# 1_ESP32_schematic_schdoc.net
KiCad netlist of a schematic drawn in Altium Designer
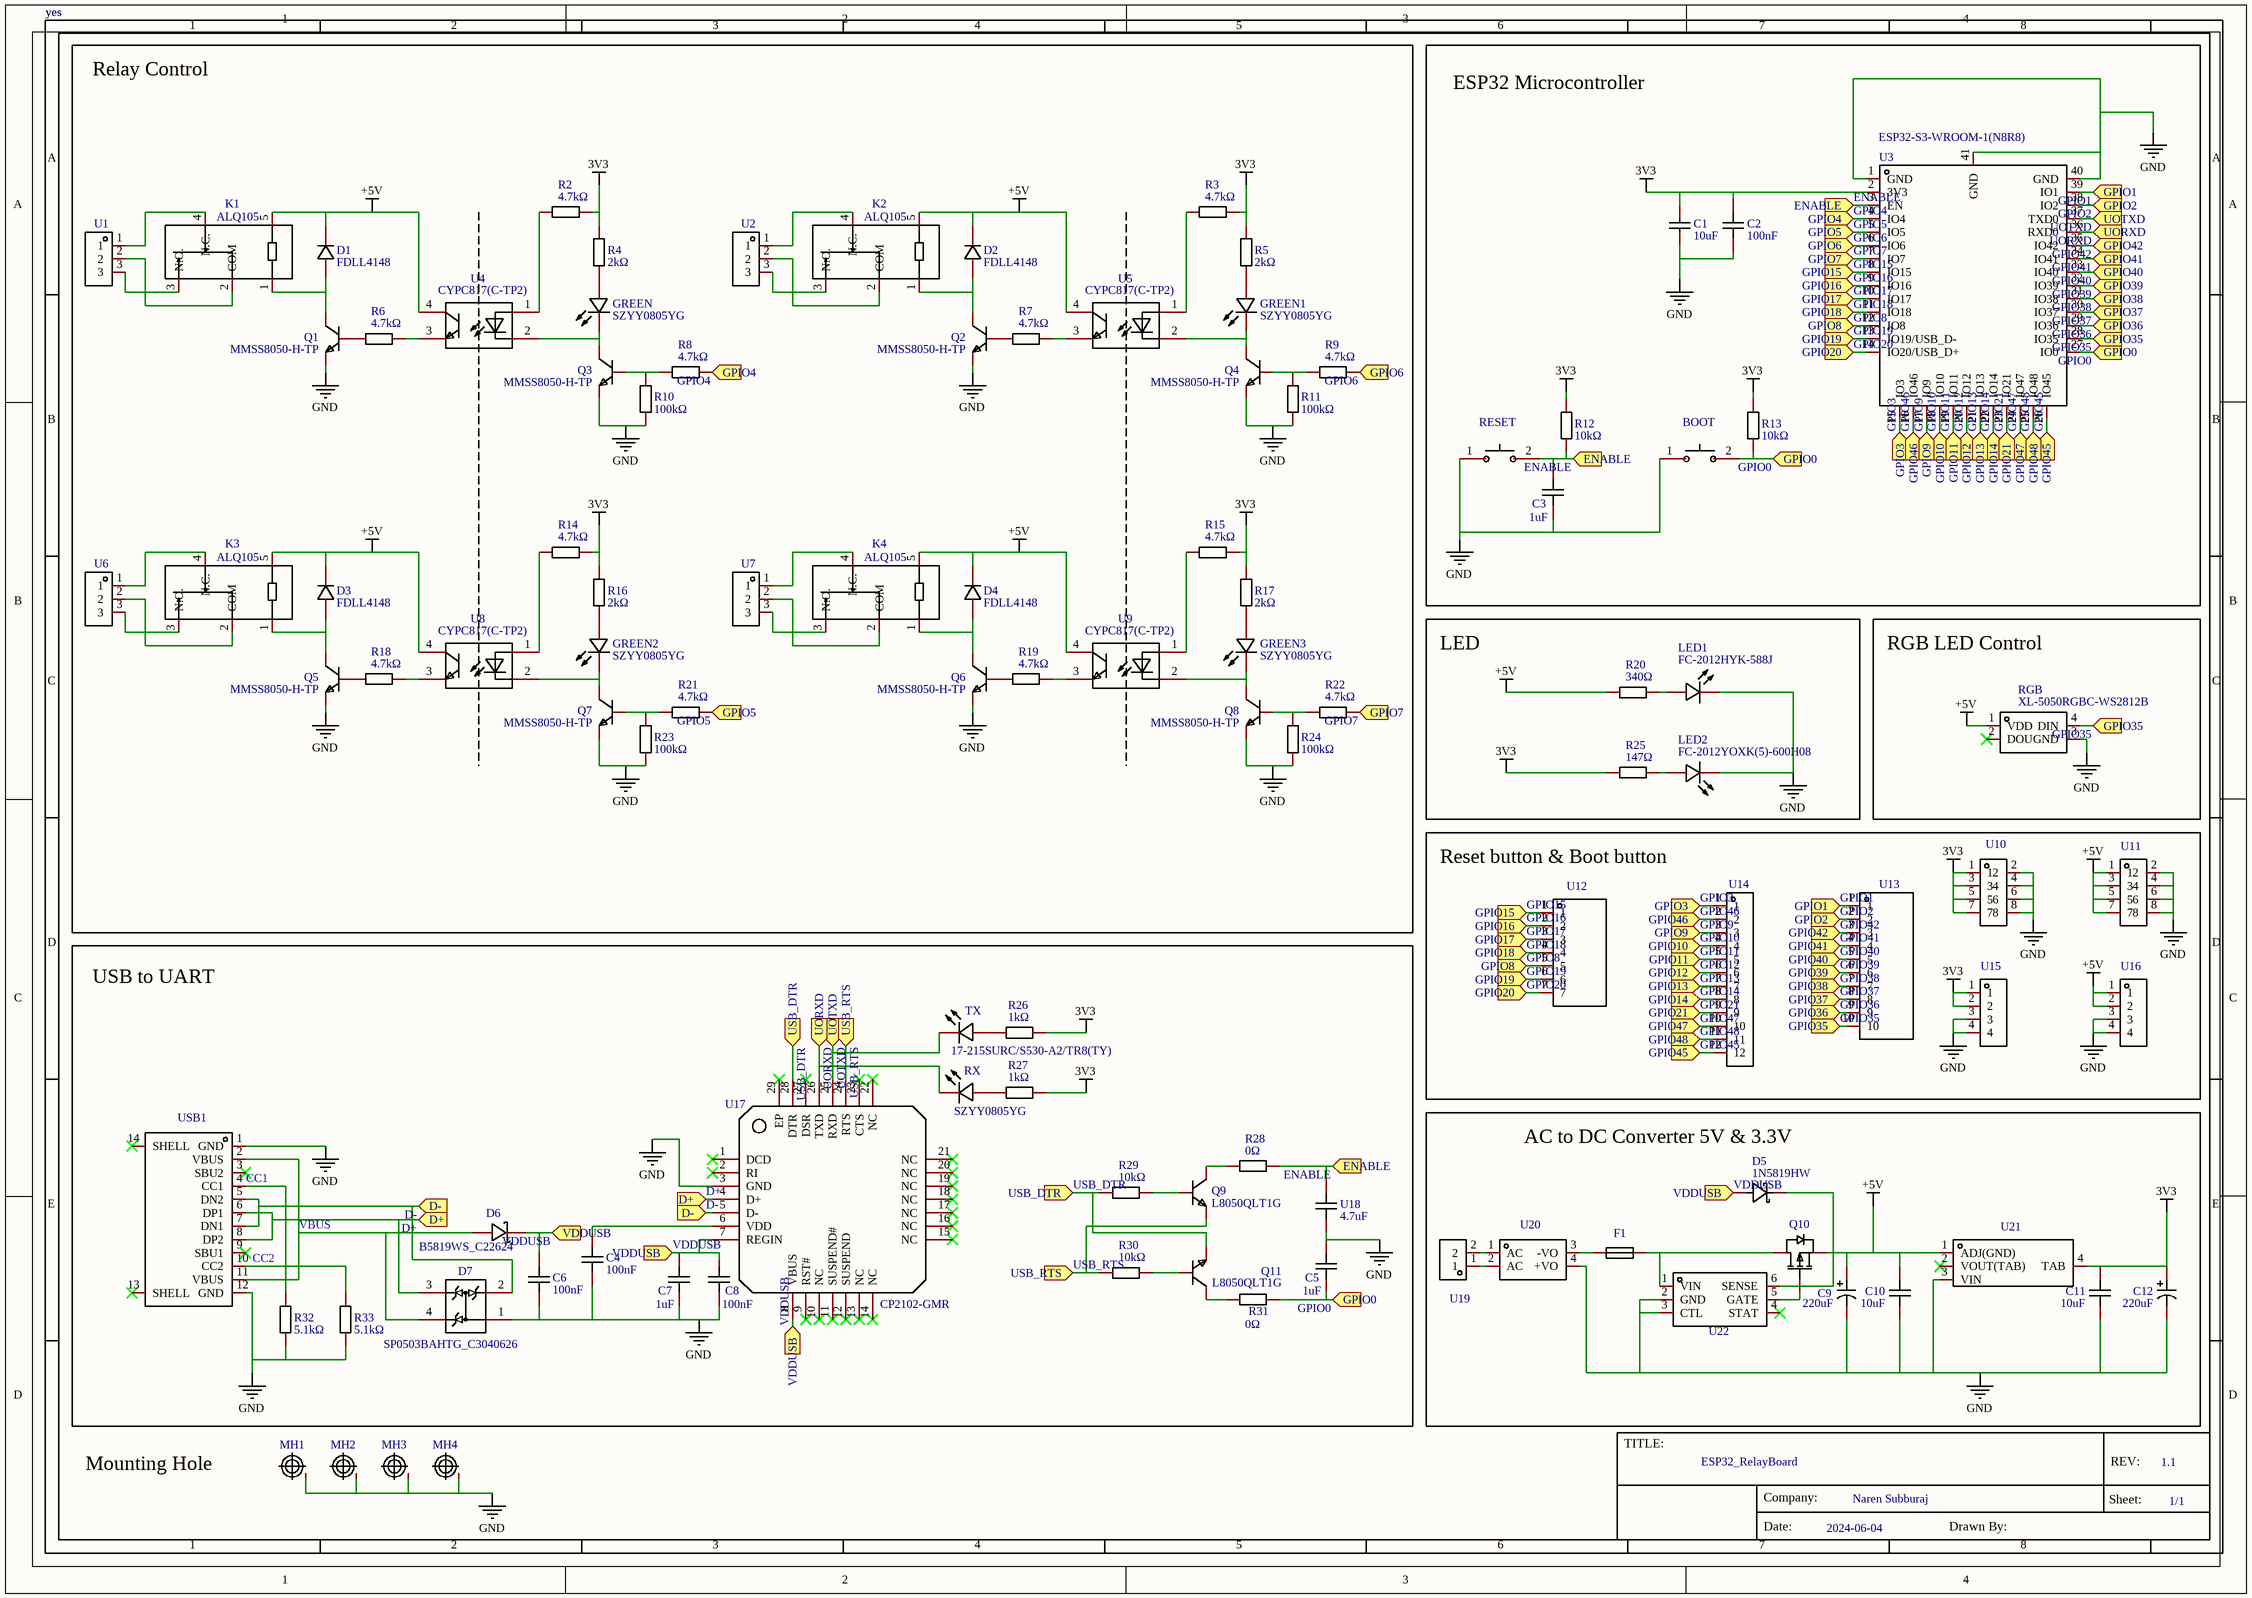
[diagram p0: 1_ESP32_schematic.schdoc.schdoc]

(export (version "E")
  (design (tool "Eeschema 10.0.6"))
  (components
    (comp (ref "BOOT")
      (value "TS-1101S-C-B-B-B-A")
      (fields (field (name "MANUFACTURER") "XKB Connectivity(中国星坤)"))
      (libsource (lib "altium-import") (part "root_0_TS-1101S-C-B-B-B-A_"))
    )
    (comp (ref "C1")
      (value "10uF")
      (fields
        (field (name "NAME") "10uF")
        (field (name "MANUFACTURER") "YAGEO(国巨)")
        (field (name "MANUFACTURER PART") "CC0402MRX5R5BB106")
      )
      (libsource (lib "altium-import") (part "root_1_10uF_"))
    )
    (comp (ref "C2")
      (value "100nF")
      (fields
        (field (name "NAME") "100nF")
        (field (name "MANUFACTURER") "HRE(芯声)")
        (field (name "MANUFACTURER PART") "CSA0402X7R104K250GT")
      )
      (libsource (lib "altium-import") (part "root_1_100nF_"))
    )
    (comp (ref "C3")
      (value "1uF")
      (fields
        (field (name "NAME") "1uF")
        (field (name "MANUFACTURER") "Chinocera(华瓷)")
        (field (name "MANUFACTURER PART") "HGC0402R5105K500NTEJ")
      )
      (libsource (lib "altium-import") (part "root_1_1uF_"))
    )
    (comp (ref "C4")
      (value "100nF")
      (fields
        (field (name "NAME") "100nF")
        (field (name "MANUFACTURER") "HRE(芯声)")
        (field (name "MANUFACTURER PART") "CSA0402X7R104K250GT")
      )
      (libsource (lib "altium-import") (part "root_1_100nF_"))
    )
    (comp (ref "C5")
      (value "1uF")
      (fields
        (field (name "NAME") "1uF")
        (field (name "MANUFACTURER") "Chinocera(华瓷)")
        (field (name "MANUFACTURER PART") "HGC0402R5105K500NTEJ")
      )
      (libsource (lib "altium-import") (part "root_1_1uF_"))
    )
    (comp (ref "C6")
      (value "100nF")
      (fields
        (field (name "NAME") "100nF")
        (field (name "MANUFACTURER") "HRE(芯声)")
        (field (name "MANUFACTURER PART") "CSA0402X7R104K250GT")
      )
      (libsource (lib "altium-import") (part "root_1_100nF_"))
    )
    (comp (ref "C7")
      (value "1uF")
      (fields
        (field (name "NAME") "1uF")
        (field (name "MANUFACTURER") "Chinocera(华瓷)")
        (field (name "MANUFACTURER PART") "HGC0402R5105K500NTEJ")
      )
      (libsource (lib "altium-import") (part "root_1_1uF_"))
    )
    (comp (ref "C8")
      (value "100nF")
      (fields
        (field (name "NAME") "100nF")
        (field (name "MANUFACTURER") "HRE(芯声)")
        (field (name "MANUFACTURER PART") "CSA0402X7R104K250GT")
      )
      (libsource (lib "altium-import") (part "root_1_100nF_"))
    )
    (comp (ref "C9")
      (value "220uF")
      (fields
        (field (name "NAME") "220uF")
        (field (name "MANUFACTURER") "SAMYOUNG(韩国三莹)")
        (field (name "MANUFACTURER PART") "MVG 16V 220UF 6.3*7.7")
      )
      (libsource (lib "altium-import") (part "root_3_220uF_"))
    )
    (comp (ref "C10")
      (value "10uF")
      (fields
        (field (name "NAME") "10uF")
        (field (name "MANUFACTURER") "FH(风华)")
        (field (name "MANUFACTURER PART") "0805F106M160NT")
      )
      (libsource (lib "") (part "root_1_10uF__1"))
    )
    (comp (ref "C11")
      (value "10uF")
      (fields
        (field (name "NAME") "10uF")
        (field (name "MANUFACTURER") "FH(风华)")
        (field (name "MANUFACTURER PART") "0805F106M160NT")
      )
      (libsource (lib "") (part "root_1_10uF__1"))
    )
    (comp (ref "C12")
      (value "220uF")
      (fields
        (field (name "NAME") "220uF")
        (field (name "MANUFACTURER") "SAMYOUNG(韩国三莹)")
        (field (name "MANUFACTURER PART") "MVG 16V 220UF 6.3*7.7")
      )
      (libsource (lib "altium-import") (part "root_3_220uF_"))
    )
    (comp (ref "D1")
      (value "FDLL4148")
      (fields (field (name "NAME") "FDLL4148") (field (name "MANUFACTURER") "onsemi(安森美)"))
      (libsource (lib "altium-import") (part "root_3_FDLL4148_"))
    )
    (comp (ref "D2")
      (value "FDLL4148")
      (fields (field (name "NAME") "FDLL4148") (field (name "MANUFACTURER") "onsemi(安森美)"))
      (libsource (lib "altium-import") (part "root_3_FDLL4148_"))
    )
    (comp (ref "D3")
      (value "FDLL4148")
      (fields (field (name "NAME") "FDLL4148") (field (name "MANUFACTURER") "onsemi(安森美)"))
      (libsource (lib "altium-import") (part "root_3_FDLL4148_"))
    )
    (comp (ref "D4")
      (value "FDLL4148")
      (fields (field (name "NAME") "FDLL4148") (field (name "MANUFACTURER") "onsemi(安森美)"))
      (libsource (lib "altium-import") (part "root_3_FDLL4148_"))
    )
    (comp (ref "D5")
      (value "1N5819HW")
      (fields (field (name "NAME") "1N5819HW") (field (name "MANUFACTURER") "TECH PUBLIC(台舟)"))
      (libsource (lib "altium-import") (part "root_2_1N5819HW_"))
    )
    (comp (ref "D6")
      (value "B5819WS_C22624")
      (fields
        (field (name "NAME") "B5819WS_C22624")
        (field (name "MANUFACTURER PART") "B5819WS")
        (field (name "MANUFACTURER") "CJ(江苏长电/长晶)")
      )
      (libsource (lib "altium-import") (part "root_2_B5819WS_C22624_"))
    )
    (comp (ref "D7")
      (value "SP0503BAHTG_C3040626")
      (fields
        (field (name "NAME") "SP0503BAHTG_C3040626")
        (field (name "MANUFACTURER") "TECH PUBLIC(台舟)")
        (field (name "MANUFACTURER PART") "SP0503BAHTG")
      )
      (libsource (lib "altium-import") (part "root_2_SP0503BAHTG_C3040626_"))
    )
    (comp (ref "F1")
      (value "BSMD0805-100-6V")
      (fields (field (name "MANUFACTURER") "BHFUSE(佰宏)"))
      (libsource (lib "altium-import") (part "root_0_BSMD0805-100-6V_"))
    )
    (comp (ref "GREEN")
      (value "SZYY0805YG")
      (fields (field (name "NAME") "SZYY0805YG") (field (name "MANUFACTURER") "yongyu(永裕光电)"))
      (libsource (lib "altium-import") (part "root_1_SZYY0805YG_"))
    )
    (comp (ref "GREEN1")
      (value "SZYY0805YG")
      (fields (field (name "NAME") "SZYY0805YG") (field (name "MANUFACTURER") "yongyu(永裕光电)"))
      (libsource (lib "altium-import") (part "root_1_SZYY0805YG_"))
    )
    (comp (ref "GREEN2")
      (value "SZYY0805YG")
      (fields (field (name "NAME") "SZYY0805YG") (field (name "MANUFACTURER") "yongyu(永裕光电)"))
      (libsource (lib "altium-import") (part "root_1_SZYY0805YG_"))
    )
    (comp (ref "GREEN3")
      (value "SZYY0805YG")
      (fields (field (name "NAME") "SZYY0805YG") (field (name "MANUFACTURER") "yongyu(永裕光电)"))
      (libsource (lib "altium-import") (part "root_1_SZYY0805YG_"))
    )
    (comp (ref "K1")
      (value "ALQ105")
      (fields (field (name "NAME") "ALQ105") (field (name "MANUFACTURER") "PANASONIC(松下)"))
      (libsource (lib "altium-import") (part "root_2_ALQ105_"))
    )
    (comp (ref "K2")
      (value "ALQ105")
      (fields (field (name "NAME") "ALQ105") (field (name "MANUFACTURER") "PANASONIC(松下)"))
      (libsource (lib "altium-import") (part "root_2_ALQ105_"))
    )
    (comp (ref "K3")
      (value "ALQ105")
      (fields (field (name "NAME") "ALQ105") (field (name "MANUFACTURER") "PANASONIC(松下)"))
      (libsource (lib "altium-import") (part "root_2_ALQ105_"))
    )
    (comp (ref "K4")
      (value "ALQ105")
      (fields (field (name "NAME") "ALQ105") (field (name "MANUFACTURER") "PANASONIC(松下)"))
      (libsource (lib "altium-import") (part "root_2_ALQ105_"))
    )
    (comp (ref "LED1")
      (value "FC-2012HYK-588J")
      (fields
        (field (name "NAME") "FC-2012HYK-588J")
        (field (name "MANUFACTURER") "国星光电")
        (field (name "MANUFACTURER PART") "NCD0805Y1")
      )
      (libsource (lib "altium-import") (part "root_0_FC-2012HYK-588J_"))
    )
    (comp (ref "LED2")
      (value "FC-2012YOXK(5)-600H08")
      (fields
        (field (name "NAME") "FC-2012YOXK(5)-600H08")
        (field (name "MANUFACTURER") "国星光电")
        (field (name "MANUFACTURER PART") "NCD0805O1")
      )
      (libsource (lib "altium-import") (part "root_2_FC-2012YOXK(5)-600H08_"))
    )
    (comp (ref "MH1")
      (value "M2-MOUNTING-HOLE")
      (libsource (lib "altium-import") (part "root_0_M2-MOUNTING-HOLE_"))
    )
    (comp (ref "MH2") (value "M2-MOUNTING-HOLE") (libsource (lib "") (part "root_0_M2-MOUNTING-HOLE__1")))
    (comp (ref "MH3") (value "M2-MOUNTING-HOLE") (libsource (lib "") (part "root_0_M2-MOUNTING-HOLE__2")))
    (comp (ref "MH4")
      (value "M2-MOUNTING-HOLE")
      (libsource (lib "altium-import") (part "root_0_M2-MOUNTING-HOLE_"))
    )
    (comp (ref "Q1")
      (value "MMSS8050-H-TP")
      (fields (field (name "NAME") "MMSS8050-H-TP") (field (name "MANUFACTURER") "MCC(美微科)"))
      (libsource (lib "altium-import") (part "root_0_MMSS8050-H-TP_"))
    )
    (comp (ref "Q2")
      (value "MMSS8050-H-TP")
      (fields (field (name "NAME") "MMSS8050-H-TP") (field (name "MANUFACTURER") "MCC(美微科)"))
      (libsource (lib "altium-import") (part "root_0_MMSS8050-H-TP_"))
    )
    (comp (ref "Q3")
      (value "MMSS8050-H-TP")
      (fields (field (name "NAME") "MMSS8050-H-TP") (field (name "MANUFACTURER") "MCC(美微科)"))
      (libsource (lib "altium-import") (part "root_0_MMSS8050-H-TP_"))
    )
    (comp (ref "Q4")
      (value "MMSS8050-H-TP")
      (fields (field (name "NAME") "MMSS8050-H-TP") (field (name "MANUFACTURER") "MCC(美微科)"))
      (libsource (lib "altium-import") (part "root_0_MMSS8050-H-TP_"))
    )
    (comp (ref "Q5")
      (value "MMSS8050-H-TP")
      (fields (field (name "NAME") "MMSS8050-H-TP") (field (name "MANUFACTURER") "MCC(美微科)"))
      (libsource (lib "altium-import") (part "root_0_MMSS8050-H-TP_"))
    )
    (comp (ref "Q6")
      (value "MMSS8050-H-TP")
      (fields (field (name "NAME") "MMSS8050-H-TP") (field (name "MANUFACTURER") "MCC(美微科)"))
      (libsource (lib "altium-import") (part "root_0_MMSS8050-H-TP_"))
    )
    (comp (ref "Q7")
      (value "MMSS8050-H-TP")
      (fields (field (name "NAME") "MMSS8050-H-TP") (field (name "MANUFACTURER") "MCC(美微科)"))
      (libsource (lib "altium-import") (part "root_0_MMSS8050-H-TP_"))
    )
    (comp (ref "Q8")
      (value "MMSS8050-H-TP")
      (fields (field (name "NAME") "MMSS8050-H-TP") (field (name "MANUFACTURER") "MCC(美微科)"))
      (libsource (lib "altium-import") (part "root_0_MMSS8050-H-TP_"))
    )
    (comp (ref "Q9")
      (value "L8050QLT1G")
      (fields (field (name "NAME") "L8050QLT1G") (field (name "MANUFACTURER") "LRC(乐山无线电)"))
      (libsource (lib "altium-import") (part "root_0_L8050QLT1G_"))
    )
    (comp (ref "Q10")
      (value "FDN306P")
      (fields (field (name "MANUFACTURER") "onsemi(安森美)"))
      (libsource (lib "altium-import") (part "root_1_FDN306P_"))
    )
    (comp (ref "Q11")
      (value "L8050QLT1G")
      (fields (field (name "NAME") "L8050QLT1G") (field (name "MANUFACTURER") "LRC(乐山无线电)"))
      (libsource (lib "altium-import") (part "root_2_L8050QLT1G_"))
    )
    (comp (ref "R2")
      (value "4.7kΩ")
      (fields
        (field (name "NAME") "4.7kΩ")
        (field (name "MANUFACTURER") "UNI-ROYAL(厚声)")
        (field (name "MANUFACTURER PART") "0805W8F4701T5E")
      )
      (libsource (lib "altium-import") (part "root_0_4.7kΩ_"))
    )
    (comp (ref "R3")
      (value "4.7kΩ")
      (fields
        (field (name "NAME") "4.7kΩ")
        (field (name "MANUFACTURER") "UNI-ROYAL(厚声)")
        (field (name "MANUFACTURER PART") "0805W8F4701T5E")
      )
      (libsource (lib "altium-import") (part "root_0_4.7kΩ_"))
    )
    (comp (ref "R4")
      (value "2kΩ")
      (fields
        (field (name "NAME") "2kΩ")
        (field (name "MANUFACTURER") "UNI-ROYAL(厚声)")
        (field (name "MANUFACTURER PART") "0805W8F2001T5E")
      )
      (libsource (lib "altium-import") (part "root_1_2kΩ_"))
    )
    (comp (ref "R5")
      (value "2kΩ")
      (fields
        (field (name "NAME") "2kΩ")
        (field (name "MANUFACTURER") "UNI-ROYAL(厚声)")
        (field (name "MANUFACTURER PART") "0805W8F2001T5E")
      )
      (libsource (lib "altium-import") (part "root_1_2kΩ_"))
    )
    (comp (ref "R6")
      (value "4.7kΩ")
      (fields
        (field (name "NAME") "4.7kΩ")
        (field (name "MANUFACTURER") "UNI-ROYAL(厚声)")
        (field (name "MANUFACTURER PART") "0805W8F4701T5E")
      )
      (libsource (lib "altium-import") (part "root_0_4.7kΩ_"))
    )
    (comp (ref "R7")
      (value "4.7kΩ")
      (fields
        (field (name "NAME") "4.7kΩ")
        (field (name "MANUFACTURER") "UNI-ROYAL(厚声)")
        (field (name "MANUFACTURER PART") "0805W8F4701T5E")
      )
      (libsource (lib "altium-import") (part "root_0_4.7kΩ_"))
    )
    (comp (ref "R8")
      (value "4.7kΩ")
      (fields
        (field (name "NAME") "4.7kΩ")
        (field (name "MANUFACTURER") "UNI-ROYAL(厚声)")
        (field (name "MANUFACTURER PART") "0805W8F4701T5E")
      )
      (libsource (lib "altium-import") (part "root_0_4.7kΩ_"))
    )
    (comp (ref "R9")
      (value "4.7kΩ")
      (fields
        (field (name "NAME") "4.7kΩ")
        (field (name "MANUFACTURER") "UNI-ROYAL(厚声)")
        (field (name "MANUFACTURER PART") "0805W8F4701T5E")
      )
      (libsource (lib "altium-import") (part "root_0_4.7kΩ_"))
    )
    (comp (ref "R10")
      (value "100kΩ")
      (fields
        (field (name "NAME") "100kΩ")
        (field (name "MANUFACTURER") "UNI-ROYAL(厚声)")
        (field (name "MANUFACTURER PART") "0805W8F1003T5E")
      )
      (libsource (lib "altium-import") (part "root_1_100kΩ_"))
    )
    (comp (ref "R11")
      (value "100kΩ")
      (fields
        (field (name "NAME") "100kΩ")
        (field (name "MANUFACTURER") "UNI-ROYAL(厚声)")
        (field (name "MANUFACTURER PART") "0805W8F1003T5E")
      )
      (libsource (lib "altium-import") (part "root_1_100kΩ_"))
    )
    (comp (ref "R12")
      (value "10kΩ")
      (fields
        (field (name "NAME") "10kΩ")
        (field (name "MANUFACTURER") "YAGEO(国巨)")
        (field (name "MANUFACTURER PART") "RT0402DRE0710KL")
      )
      (libsource (lib "altium-import") (part "root_1_10kΩ_"))
    )
    (comp (ref "R13")
      (value "10kΩ")
      (fields
        (field (name "NAME") "10kΩ")
        (field (name "MANUFACTURER") "YAGEO(国巨)")
        (field (name "MANUFACTURER PART") "RT0402DRE0710KL")
      )
      (libsource (lib "altium-import") (part "root_1_10kΩ_"))
    )
    (comp (ref "R14")
      (value "4.7kΩ")
      (fields
        (field (name "NAME") "4.7kΩ")
        (field (name "MANUFACTURER") "UNI-ROYAL(厚声)")
        (field (name "MANUFACTURER PART") "0805W8F4701T5E")
      )
      (libsource (lib "altium-import") (part "root_0_4.7kΩ_"))
    )
    (comp (ref "R15")
      (value "4.7kΩ")
      (fields
        (field (name "NAME") "4.7kΩ")
        (field (name "MANUFACTURER") "UNI-ROYAL(厚声)")
        (field (name "MANUFACTURER PART") "0805W8F4701T5E")
      )
      (libsource (lib "altium-import") (part "root_0_4.7kΩ_"))
    )
    (comp (ref "R16")
      (value "2kΩ")
      (fields
        (field (name "NAME") "2kΩ")
        (field (name "MANUFACTURER") "UNI-ROYAL(厚声)")
        (field (name "MANUFACTURER PART") "0805W8F2001T5E")
      )
      (libsource (lib "altium-import") (part "root_1_2kΩ_"))
    )
    (comp (ref "R17")
      (value "2kΩ")
      (fields
        (field (name "NAME") "2kΩ")
        (field (name "MANUFACTURER") "UNI-ROYAL(厚声)")
        (field (name "MANUFACTURER PART") "0805W8F2001T5E")
      )
      (libsource (lib "altium-import") (part "root_1_2kΩ_"))
    )
    (comp (ref "R18")
      (value "4.7kΩ")
      (fields
        (field (name "NAME") "4.7kΩ")
        (field (name "MANUFACTURER") "UNI-ROYAL(厚声)")
        (field (name "MANUFACTURER PART") "0805W8F4701T5E")
      )
      (libsource (lib "altium-import") (part "root_0_4.7kΩ_"))
    )
    (comp (ref "R19")
      (value "4.7kΩ")
      (fields
        (field (name "NAME") "4.7kΩ")
        (field (name "MANUFACTURER") "UNI-ROYAL(厚声)")
        (field (name "MANUFACTURER PART") "0805W8F4701T5E")
      )
      (libsource (lib "altium-import") (part "root_0_4.7kΩ_"))
    )
    (comp (ref "R20")
      (value "340Ω")
      (fields
        (field (name "NAME") "340Ω")
        (field (name "MANUFACTURER") "LIZ(丽智电子)")
        (field (name "MANUFACTURER PART") "CR0805F83400G")
      )
      (libsource (lib "altium-import") (part "root_0_340Ω_"))
    )
    (comp (ref "R21")
      (value "4.7kΩ")
      (fields
        (field (name "NAME") "4.7kΩ")
        (field (name "MANUFACTURER") "UNI-ROYAL(厚声)")
        (field (name "MANUFACTURER PART") "0805W8F4701T5E")
      )
      (libsource (lib "altium-import") (part "root_0_4.7kΩ_"))
    )
    (comp (ref "R22")
      (value "4.7kΩ")
      (fields
        (field (name "NAME") "4.7kΩ")
        (field (name "MANUFACTURER") "UNI-ROYAL(厚声)")
        (field (name "MANUFACTURER PART") "0805W8F4701T5E")
      )
      (libsource (lib "altium-import") (part "root_0_4.7kΩ_"))
    )
    (comp (ref "R23")
      (value "100kΩ")
      (fields
        (field (name "NAME") "100kΩ")
        (field (name "MANUFACTURER") "UNI-ROYAL(厚声)")
        (field (name "MANUFACTURER PART") "0805W8F1003T5E")
      )
      (libsource (lib "altium-import") (part "root_1_100kΩ_"))
    )
    (comp (ref "R24")
      (value "100kΩ")
      (fields
        (field (name "NAME") "100kΩ")
        (field (name "MANUFACTURER") "UNI-ROYAL(厚声)")
        (field (name "MANUFACTURER PART") "0805W8F1003T5E")
      )
      (libsource (lib "altium-import") (part "root_1_100kΩ_"))
    )
    (comp (ref "R25")
      (value "147Ω")
      (fields
        (field (name "NAME") "147Ω")
        (field (name "MANUFACTURER") "BOURNS")
        (field (name "MANUFACTURER PART") "CR0805-FX-1470ELF")
      )
      (libsource (lib "altium-import") (part "root_0_147Ω_"))
    )
    (comp (ref "R26")
      (value "1kΩ")
      (fields
        (field (name "NAME") "1kΩ")
        (field (name "MANUFACTURER") "Tyohm(幸亚电阻)")
        (field (name "MANUFACTURER PART") "RMC08051K5%N")
      )
      (libsource (lib "altium-import") (part "root_2_1kΩ_"))
    )
    (comp (ref "R27")
      (value "1kΩ")
      (fields
        (field (name "NAME") "1kΩ")
        (field (name "MANUFACTURER") "Tyohm(幸亚电阻)")
        (field (name "MANUFACTURER PART") "RMC08051K5%N")
      )
      (libsource (lib "altium-import") (part "root_2_1kΩ_"))
    )
    (comp (ref "R28")
      (value "0Ω")
      (fields
        (field (name "NAME") "0Ω")
        (field (name "MANUFACTURER") "YAGEO(国巨)")
        (field (name "MANUFACTURER PART") "RC0402FR-070RL")
      )
      (libsource (lib "altium-import") (part "root_0_0Ω_"))
    )
    (comp (ref "R29")
      (value "10kΩ")
      (fields
        (field (name "NAME") "10kΩ")
        (field (name "MANUFACTURER") "YAGEO(国巨)")
        (field (name "MANUFACTURER PART") "RT0402DRE0710KL")
      )
      (libsource (lib "altium-import") (part "root_0_10kΩ_"))
    )
    (comp (ref "R30")
      (value "10kΩ")
      (fields
        (field (name "NAME") "10kΩ")
        (field (name "MANUFACTURER") "YAGEO(国巨)")
        (field (name "MANUFACTURER PART") "RT0402DRE0710KL")
      )
      (libsource (lib "altium-import") (part "root_0_10kΩ_"))
    )
    (comp (ref "R31")
      (value "0Ω")
      (fields
        (field (name "NAME") "0Ω")
        (field (name "MANUFACTURER") "YAGEO(国巨)")
        (field (name "MANUFACTURER PART") "RC0402FR-070RL")
      )
      (libsource (lib "altium-import") (part "root_0_0Ω_"))
    )
    (comp (ref "R32")
      (value "5.1kΩ")
      (fields
        (field (name "NAME") "5.1kΩ")
        (field (name "MANUFACTURER") "Tyohm(幸亚电阻)")
        (field (name "MANUFACTURER PART") "RMC04025.1K1%N")
      )
      (libsource (lib "altium-import") (part "root_1_5.1kΩ_"))
    )
    (comp (ref "R33")
      (value "5.1kΩ")
      (fields
        (field (name "NAME") "5.1kΩ")
        (field (name "MANUFACTURER") "Tyohm(幸亚电阻)")
        (field (name "MANUFACTURER PART") "RMC04025.1K1%N")
      )
      (libsource (lib "altium-import") (part "root_1_5.1kΩ_"))
    )
    (comp (ref "RESET")
      (value "TS-1101S-C-B-B-B-A")
      (fields (field (name "MANUFACTURER") "XKB Connectivity(中国星坤)"))
      (libsource (lib "altium-import") (part "root_0_TS-1101S-C-B-B-B-A_"))
    )
    (comp (ref "RGB")
      (value "XL-5050RGBC-WS2812B")
      (fields (field (name "NAME") "XL-5050RGBC-WS2812B") (field (name "MANUFACTURER") "XINGLIGHT(成兴光)"))
      (libsource (lib "altium-import") (part "root_0_XL-5050RGBC-WS2812B_"))
    )
    (comp (ref "RX")
      (value "SZYY0805YG")
      (fields (field (name "NAME") "SZYY0805YG") (field (name "MANUFACTURER") "yongyu(永裕光电)"))
      (libsource (lib "altium-import") (part "root_0_SZYY0805YG_"))
    )
    (comp (ref "TX")
      (value "17-215SURC/S530-A2/TR8(TY)")
      (fields
        (field (name "NAME") "17-215SURC/S530-A2/TR8(TY)")
        (field (name "MANUFACTURER") "EVERLIGHT(亿光)")
        (field (name "MANUFACTURER PART") "17-215SURC/S530-A2/TR8")
      )
      (libsource (lib "altium-import") (part "root_0_17-215SURC/S530-A2/TR8(TY)_"))
    )
    (comp (ref "U1")
      (value "DB128L-5.08-3P-BK-S")
      (fields (field (name "MANUFACTURER") "DORABO(地博电气)"))
      (libsource (lib "altium-import") (part "root_0_DB128L-5.08-3P-BK-S_"))
    )
    (comp (ref "U2")
      (value "DB128L-5.08-3P-BK-S")
      (fields (field (name "MANUFACTURER") "DORABO(地博电气)"))
      (libsource (lib "altium-import") (part "root_0_DB128L-5.08-3P-BK-S_"))
    )
    (comp (ref "U3")
      (value "ESP32-S3-WROOM-1(N8R8)")
      (fields
        (field (name "NAME") "ESP32-S3-WROOM-1(N8R8)")
        (field (name "MANUFACTURER") "ESPRESSIF(乐鑫)")
        (field (name "MANUFACTURER PART") "ESP32-S3-WROOM-1-N8R8")
      )
      (libsource (lib "altium-import") (part "root_0_ESP32-S3-WROOM-1(N8R8)_"))
    )
    (comp (ref "U4")
      (value "CYPC817(C-TP2)")
      (fields (field (name "NAME") "CYPC817(C-TP2)") (field (name "MANUFACTURER") "OCIC(卓睿科)"))
      (libsource (lib "altium-import") (part "root_0_CYPC817(C-TP2)_"))
    )
    (comp (ref "U5")
      (value "CYPC817(C-TP2)")
      (fields (field (name "NAME") "CYPC817(C-TP2)") (field (name "MANUFACTURER") "OCIC(卓睿科)"))
      (libsource (lib "altium-import") (part "root_0_CYPC817(C-TP2)_"))
    )
    (comp (ref "U6")
      (value "DB128L-5.08-3P-BK-S")
      (fields (field (name "MANUFACTURER") "DORABO(地博电气)"))
      (libsource (lib "altium-import") (part "root_0_DB128L-5.08-3P-BK-S_"))
    )
    (comp (ref "U7")
      (value "DB128L-5.08-3P-BK-S")
      (fields (field (name "MANUFACTURER") "DORABO(地博电气)"))
      (libsource (lib "altium-import") (part "root_0_DB128L-5.08-3P-BK-S_"))
    )
    (comp (ref "U8")
      (value "CYPC817(C-TP2)")
      (fields (field (name "NAME") "CYPC817(C-TP2)") (field (name "MANUFACTURER") "OCIC(卓睿科)"))
      (libsource (lib "altium-import") (part "root_0_CYPC817(C-TP2)_"))
    )
    (comp (ref "U9")
      (value "CYPC817(C-TP2)")
      (fields (field (name "NAME") "CYPC817(C-TP2)") (field (name "MANUFACTURER") "OCIC(卓睿科)"))
      (libsource (lib "altium-import") (part "root_0_CYPC817(C-TP2)_"))
    )
    (comp (ref "U10")
      (value "ZX-PM2.54-2-4PY")
      (fields (field (name "MANUFACTURER") "Megastar(兆星)"))
      (libsource (lib "altium-import") (part "root_0_ZX-PM2.54-2-4PY_"))
    )
    (comp (ref "U11")
      (value "ZX-PM2.54-2-4PY")
      (fields (field (name "MANUFACTURER") "Megastar(兆星)"))
      (libsource (lib "altium-import") (part "root_0_ZX-PM2.54-2-4PY_"))
    )
    (comp (ref "U12")
      (value "A2541HWV-7P")
      (fields (field (name "MANUFACTURER") "CJT(长江连接器)"))
      (libsource (lib "altium-import") (part "root_0_A2541HWV-7P_"))
    )
    (comp (ref "U13")
      (value "A2541HWV-10P")
      (fields (field (name "MANUFACTURER") "CJT(长江连接器)"))
      (libsource (lib "altium-import") (part "root_0_A2541HWV-10P_"))
    )
    (comp (ref "U14")
      (value "ZX-PM2.54-1-12PY")
      (fields (field (name "MANUFACTURER") "Megastar(兆星)"))
      (libsource (lib "altium-import") (part "root_0_ZX-PM2.54-1-12PY_"))
    )
    (comp (ref "U15")
      (value "HB-PH3-25414PB2GOP")
      (fields (field (name "MANUFACTURER") "HANBO(汉博)"))
      (libsource (lib "altium-import") (part "root_0_HB-PH3-25414PB2GOP_"))
    )
    (comp (ref "U16")
      (value "HB-PH3-25414PB2GOP")
      (fields (field (name "MANUFACTURER") "HANBO(汉博)"))
      (libsource (lib "altium-import") (part "root_0_HB-PH3-25414PB2GOP_"))
    )
    (comp (ref "U17")
      (value "CP2102-GMR")
      (fields (field (name "NAME") "CP2102-GMR") (field (name "MANUFACTURER") "SKYWORKS/SILICON LABS(芯科)"))
      (libsource (lib "altium-import") (part "root_0_CP2102-GMR_"))
    )
    (comp (ref "U18")
      (value "4.7uF")
      (fields
        (field (name "NAME") "4.7uF")
        (field (name "MANUFACTURER") "Chinocera(华瓷)")
        (field (name "MANUFACTURER PART") "HGC0402R5475K100NTEJ")
      )
      (libsource (lib "altium-import") (part "root_1_4.7uF_"))
    )
    (comp (ref "U19")
      (value "DB128L-5.08-2P-BK-S")
      (fields (field (name "MANUFACTURER") "DORABO(地博电气)"))
      (libsource (lib "altium-import") (part "root_0_DB128L-5.08-2P-BK-S_"))
    )
    (comp (ref "U20")
      (value "HLK-10M05")
      (fields (field (name "MANUFACTURER") "HI-LINK(海凌科)"))
      (libsource (lib "altium-import") (part "root_0_HLK-10M05_"))
    )
    (comp (ref "U21")
      (value "AMS1117-3.3_C347222")
      (fields (field (name "MANUFACTURER") "UMW(友台半导体)") (field (name "MANUFACTURER PART") "AMS1117-3.3"))
      (libsource (lib "altium-import") (part "root_0_AMS1117-3.3_C347222_"))
    )
    (comp (ref "U22")
      (value "LTC4412HVIS6#TRPBF")
      (fields (field (name "MANUFACTURER") "ADI(亚德诺)"))
      (libsource (lib "altium-import") (part "root_0_LTC4412HVIS6#TRPBF_"))
    )
    (comp (ref "USB1")
      (value "TYPE-C 16PIN 2MD(073)")
      (fields (field (name "MANUFACTURER") "SHOU HAN(首韩)"))
      (libsource (lib "altium-import") (part "root_0_TYPE-C 16PIN 2MD(073)_"))
    )
  )
  (nets
    (net (code "1") (name "+5V") (class "Default")
      (node (ref "C10") (pin "2") (pinfunction "2_2") (pintype "passive"))
      (node (ref "C9") (pin "1") (pinfunction "1_1") (pintype "passive"))
      (node (ref "D1") (pin "1") (pinfunction "C_1") (pintype "passive"))
      (node (ref "D2") (pin "1") (pinfunction "C_1") (pintype "passive"))
      (node (ref "D3") (pin "1") (pinfunction "C_1") (pintype "passive"))
      (node (ref "D4") (pin "1") (pinfunction "C_1") (pintype "passive"))
      (node (ref "D5") (pin "1") (pinfunction "K_1") (pintype "passive"))
      (node (ref "K1") (pin "5") (pinfunction "5_5") (pintype "passive"))
      (node (ref "K2") (pin "5") (pinfunction "5_5") (pintype "passive"))
      (node (ref "K3") (pin "5") (pinfunction "5_5") (pintype "passive"))
      (node (ref "K4") (pin "5") (pinfunction "5_5") (pintype "passive"))
      (node (ref "Q10") (pin "2") (pinfunction "S_2") (pintype "passive"))
      (node (ref "R20") (pin "1") (pinfunction "1_1") (pintype "passive"))
      (node (ref "RGB") (pin "1") (pinfunction "VDD_1") (pintype "passive"))
      (node (ref "U11") (pin "1") (pinfunction "1_1") (pintype "passive"))
      (node (ref "U11") (pin "3") (pinfunction "3_3") (pintype "passive"))
      (node (ref "U11") (pin "5") (pinfunction "5_5") (pintype "passive"))
      (node (ref "U11") (pin "7") (pinfunction "7_7") (pintype "passive"))
      (node (ref "U16") (pin "1") (pinfunction "1_1") (pintype "passive"))
      (node (ref "U16") (pin "2") (pinfunction "2_2") (pintype "passive"))
      (node (ref "U21") (pin "1") (pinfunction "ADJ(GND)_1") (pintype "passive"))
      (node (ref "U22") (pin "6") (pinfunction "SENSE_6") (pintype "passive"))
      (node (ref "U4") (pin "4") (pinfunction "COL_4") (pintype "passive"))
      (node (ref "U5") (pin "4") (pinfunction "COL_4") (pintype "passive"))
      (node (ref "U8") (pin "4") (pinfunction "COL_4") (pintype "passive"))
      (node (ref "U9") (pin "4") (pinfunction "COL_4") (pintype "passive"))
    )
    (net (code "2") (name "/CC1") (class "Default")
      (node (ref "R32") (pin "2") (pinfunction "2_2") (pintype "passive"))
      (node (ref "USB1") (pin "4") (pinfunction "CC1_4") (pintype "passive"))
    )
    (net (code "3") (name "/CC2") (class "Default")
      (node (ref "R33") (pin "2") (pinfunction "2_2") (pintype "passive"))
      (node (ref "USB1") (pin "10") (pinfunction "CC2_10") (pintype "passive"))
    )
    (net (code "4") (name "/D+") (class "Default")
      (node (ref "D7") (pin "3") (pinfunction "3_3") (pintype "passive"))
      (node (ref "U17") (pin "4") (pinfunction "D+_4") (pintype "passive"))
      (node (ref "USB1") (pin "6") (pinfunction "DP1_6") (pintype "passive"))
      (node (ref "USB1") (pin "8") (pinfunction "DP2_8") (pintype "passive"))
    )
    (net (code "5") (name "/D-") (class "Default")
      (node (ref "D7") (pin "2") (pinfunction "2_2") (pintype "passive"))
      (node (ref "U17") (pin "5") (pinfunction "D-_5") (pintype "passive"))
      (node (ref "USB1") (pin "5") (pinfunction "DN2_5") (pintype "passive"))
      (node (ref "USB1") (pin "7") (pinfunction "DN1_7") (pintype "passive"))
    )
    (net (code "6") (name "/ENABLE") (class "Default")
      (node (ref "C3") (pin "2") (pinfunction "2_2") (pintype "passive"))
      (node (ref "R12") (pin "1") (pinfunction "1_1") (pintype "passive"))
      (node (ref "R28") (pin "2") (pinfunction "2_2") (pintype "passive"))
      (node (ref "RESET") (pin "2") (pinfunction "2_2") (pintype "passive"))
      (node (ref "U18") (pin "2") (pinfunction "2_2") (pintype "passive"))
      (node (ref "U3") (pin "3") (pinfunction "EN_3") (pintype "passive"))
    )
    (net (code "7") (name "/GPIO0") (class "Default")
      (node (ref "BOOT") (pin "2") (pinfunction "2_2") (pintype "passive"))
      (node (ref "C5") (pin "1") (pinfunction "1_1") (pintype "passive"))
      (node (ref "R13") (pin "1") (pinfunction "1_1") (pintype "passive"))
      (node (ref "R31") (pin "2") (pinfunction "2_2") (pintype "passive"))
      (node (ref "U3") (pin "27") (pinfunction "IO0_27") (pintype "passive"))
    )
    (net (code "8") (name "/GPIO1") (class "Default")
      (node (ref "U13") (pin "1") (pinfunction "1_1") (pintype "passive"))
      (node (ref "U3") (pin "39") (pinfunction "IO1_39") (pintype "passive"))
    )
    (net (code "9") (name "/GPIO2") (class "Default")
      (node (ref "U13") (pin "2") (pinfunction "2_2") (pintype "passive"))
      (node (ref "U3") (pin "38") (pinfunction "IO2_38") (pintype "passive"))
    )
    (net (code "10") (name "/GPIO3") (class "Default")
      (node (ref "U14") (pin "1") (pinfunction "1_1") (pintype "passive"))
      (node (ref "U3") (pin "15") (pinfunction "IO3_15") (pintype "passive"))
    )
    (net (code "11") (name "/GPIO4") (class "Default")
      (node (ref "R8") (pin "2") (pinfunction "2_2") (pintype "passive"))
      (node (ref "U3") (pin "4") (pinfunction "IO4_4") (pintype "passive"))
    )
    (net (code "12") (name "/GPIO5") (class "Default")
      (node (ref "R21") (pin "2") (pinfunction "2_2") (pintype "passive"))
      (node (ref "U3") (pin "5") (pinfunction "IO5_5") (pintype "passive"))
    )
    (net (code "13") (name "/GPIO6") (class "Default")
      (node (ref "R9") (pin "2") (pinfunction "2_2") (pintype "passive"))
      (node (ref "U3") (pin "6") (pinfunction "IO6_6") (pintype "passive"))
    )
    (net (code "14") (name "/GPIO7") (class "Default")
      (node (ref "R22") (pin "2") (pinfunction "2_2") (pintype "passive"))
      (node (ref "U3") (pin "7") (pinfunction "IO7_7") (pintype "passive"))
    )
    (net (code "15") (name "/GPIO8") (class "Default")
      (node (ref "U12") (pin "5") (pinfunction "5_5") (pintype "passive"))
      (node (ref "U3") (pin "12") (pinfunction "IO8_12") (pintype "passive"))
    )
    (net (code "16") (name "/GPIO9") (class "Default")
      (node (ref "U14") (pin "3") (pinfunction "3_3") (pintype "passive"))
      (node (ref "U3") (pin "17") (pinfunction "IO9_17") (pintype "passive"))
    )
    (net (code "17") (name "/GPIO10") (class "Default")
      (node (ref "U14") (pin "4") (pinfunction "4_4") (pintype "passive"))
      (node (ref "U3") (pin "18") (pinfunction "IO10_18") (pintype "passive"))
    )
    (net (code "18") (name "/GPIO11") (class "Default")
      (node (ref "U14") (pin "5") (pinfunction "5_5") (pintype "passive"))
      (node (ref "U3") (pin "19") (pinfunction "IO11_19") (pintype "passive"))
    )
    (net (code "19") (name "/GPIO12") (class "Default")
      (node (ref "U14") (pin "6") (pinfunction "6_6") (pintype "passive"))
      (node (ref "U3") (pin "20") (pinfunction "IO12_20") (pintype "passive"))
    )
    (net (code "20") (name "/GPIO13") (class "Default")
      (node (ref "U14") (pin "7") (pinfunction "7_7") (pintype "passive"))
      (node (ref "U3") (pin "21") (pinfunction "IO13_21") (pintype "passive"))
    )
    (net (code "21") (name "/GPIO14") (class "Default")
      (node (ref "U14") (pin "8") (pinfunction "8_8") (pintype "passive"))
      (node (ref "U3") (pin "22") (pinfunction "IO14_22") (pintype "passive"))
    )
    (net (code "22") (name "/GPIO15") (class "Default")
      (node (ref "U12") (pin "1") (pinfunction "1_1") (pintype "passive"))
      (node (ref "U3") (pin "8") (pinfunction "IO15_8") (pintype "passive"))
    )
    (net (code "23") (name "/GPIO16") (class "Default")
      (node (ref "U12") (pin "2") (pinfunction "2_2") (pintype "passive"))
      (node (ref "U3") (pin "9") (pinfunction "IO16_9") (pintype "passive"))
    )
    (net (code "24") (name "/GPIO17") (class "Default")
      (node (ref "U12") (pin "3") (pinfunction "3_3") (pintype "passive"))
      (node (ref "U3") (pin "10") (pinfunction "IO17_10") (pintype "passive"))
    )
    (net (code "25") (name "/GPIO18") (class "Default")
      (node (ref "U12") (pin "4") (pinfunction "4_4") (pintype "passive"))
      (node (ref "U3") (pin "11") (pinfunction "IO18_11") (pintype "passive"))
    )
    (net (code "26") (name "/GPIO19") (class "Default")
      (node (ref "U12") (pin "6") (pinfunction "6_6") (pintype "passive"))
      (node (ref "U3") (pin "13") (pinfunction "IO19/USB_D-_13") (pintype "passive"))
    )
    (net (code "27") (name "/GPIO20") (class "Default")
      (node (ref "U12") (pin "7") (pinfunction "7_7") (pintype "passive"))
      (node (ref "U3") (pin "14") (pinfunction "IO20/USB_D+_14") (pintype "passive"))
    )
    (net (code "28") (name "/GPIO21") (class "Default")
      (node (ref "U14") (pin "9") (pinfunction "9_9") (pintype "passive"))
      (node (ref "U3") (pin "23") (pinfunction "IO21_23") (pintype "passive"))
    )
    (net (code "29") (name "/GPIO35") (class "Default")
      (node (ref "RGB") (pin "4") (pinfunction "DIN_4") (pintype "passive"))
      (node (ref "U13") (pin "10") (pinfunction "10_10") (pintype "passive"))
      (node (ref "U3") (pin "28") (pinfunction "IO35_28") (pintype "passive"))
    )
    (net (code "30") (name "/GPIO36") (class "Default")
      (node (ref "U13") (pin "9") (pinfunction "9_9") (pintype "passive"))
      (node (ref "U3") (pin "29") (pinfunction "IO36_29") (pintype "passive"))
    )
    (net (code "31") (name "/GPIO37") (class "Default")
      (node (ref "U13") (pin "8") (pinfunction "8_8") (pintype "passive"))
      (node (ref "U3") (pin "30") (pinfunction "IO37_30") (pintype "passive"))
    )
    (net (code "32") (name "/GPIO38") (class "Default")
      (node (ref "U13") (pin "7") (pinfunction "7_7") (pintype "passive"))
      (node (ref "U3") (pin "31") (pinfunction "IO38_31") (pintype "passive"))
    )
    (net (code "33") (name "/GPIO39") (class "Default")
      (node (ref "U13") (pin "6") (pinfunction "6_6") (pintype "passive"))
      (node (ref "U3") (pin "32") (pinfunction "IO39_32") (pintype "passive"))
    )
    (net (code "34") (name "/GPIO40") (class "Default")
      (node (ref "U13") (pin "5") (pinfunction "5_5") (pintype "passive"))
      (node (ref "U3") (pin "33") (pinfunction "IO40_33") (pintype "passive"))
    )
    (net (code "35") (name "/GPIO41") (class "Default")
      (node (ref "U13") (pin "4") (pinfunction "4_4") (pintype "passive"))
      (node (ref "U3") (pin "34") (pinfunction "IO41_34") (pintype "passive"))
    )
    (net (code "36") (name "/GPIO42") (class "Default")
      (node (ref "U13") (pin "3") (pinfunction "3_3") (pintype "passive"))
      (node (ref "U3") (pin "35") (pinfunction "IO42_35") (pintype "passive"))
    )
    (net (code "37") (name "/GPIO45") (class "Default")
      (node (ref "U14") (pin "12") (pinfunction "12_12") (pintype "passive"))
      (node (ref "U3") (pin "26") (pinfunction "IO45_26") (pintype "passive"))
    )
    (net (code "38") (name "/GPIO46") (class "Default")
      (node (ref "U14") (pin "2") (pinfunction "2_2") (pintype "passive"))
      (node (ref "U3") (pin "16") (pinfunction "IO46_16") (pintype "passive"))
    )
    (net (code "39") (name "/GPIO47") (class "Default")
      (node (ref "U14") (pin "10") (pinfunction "10_10") (pintype "passive"))
      (node (ref "U3") (pin "24") (pinfunction "IO47_24") (pintype "passive"))
    )
    (net (code "40") (name "/GPIO48") (class "Default")
      (node (ref "U14") (pin "11") (pinfunction "11_11") (pintype "passive"))
      (node (ref "U3") (pin "25") (pinfunction "IO48_25") (pintype "passive"))
    )
    (net (code "41") (name "/UORXD") (class "Default")
      (node (ref "RX") (pin "2") (pinfunction "-_2") (pintype "passive"))
      (node (ref "U17") (pin "26") (pinfunction "TXD_26") (pintype "passive"))
      (node (ref "U3") (pin "36") (pinfunction "RXD0_36") (pintype "passive"))
    )
    (net (code "42") (name "/UOTXD") (class "Default")
      (node (ref "TX") (pin "1") (pinfunction "K_1") (pintype "passive"))
      (node (ref "U17") (pin "25") (pinfunction "RXD_25") (pintype "passive"))
      (node (ref "U3") (pin "37") (pinfunction "TXD0_37") (pintype "passive"))
    )
    (net (code "43") (name "/USB_DTR") (class "Default")
      (node (ref "Q11") (pin "2") (pinfunction "E_2") (pintype "passive"))
      (node (ref "R29") (pin "1") (pinfunction "1_1") (pintype "passive"))
      (node (ref "U17") (pin "28") (pinfunction "DTR_28") (pintype "passive"))
    )
    (net (code "44") (name "/USB_RTS") (class "Default")
      (node (ref "Q9") (pin "2") (pinfunction "E_2") (pintype "passive"))
      (node (ref "R30") (pin "1") (pinfunction "1_1") (pintype "passive"))
      (node (ref "U17") (pin "24") (pinfunction "RTS_24") (pintype "passive"))
    )
    (net (code "45") (name "/VBUS") (class "Default")
      (node (ref "D6") (pin "2") (pinfunction "A_2") (pintype "passive"))
      (node (ref "D7") (pin "4") (pinfunction "4_4") (pintype "passive"))
      (node (ref "USB1") (pin "11") (pinfunction "VBUS_11") (pintype "passive"))
      (node (ref "USB1") (pin "2") (pinfunction "VBUS_2") (pintype "passive"))
    )
    (net (code "46") (name "/VDDUSB") (class "Default")
      (node (ref "C6") (pin "2") (pinfunction "2_2") (pintype "passive"))
      (node (ref "C7") (pin "2") (pinfunction "2_2") (pintype "passive"))
      (node (ref "C8") (pin "2") (pinfunction "2_2") (pintype "passive"))
      (node (ref "D5") (pin "2") (pinfunction "A_2") (pintype "passive"))
      (node (ref "D6") (pin "1") (pinfunction "K_1") (pintype "passive"))
      (node (ref "U17") (pin "7") (pinfunction "REGIN_7") (pintype "passive"))
      (node (ref "U17") (pin "8") (pinfunction "VBUS_8") (pintype "passive"))
    )
    (net (code "47") (name "3V3") (class "Default")
      (node (ref "C1") (pin "2") (pinfunction "2_2") (pintype "passive"))
      (node (ref "C11") (pin "2") (pinfunction "2_2") (pintype "passive"))
      (node (ref "C12") (pin "1") (pinfunction "1_1") (pintype "passive"))
      (node (ref "C2") (pin "2") (pinfunction "2_2") (pintype "passive"))
      (node (ref "R12") (pin "2") (pinfunction "2_2") (pintype "passive"))
      (node (ref "R13") (pin "2") (pinfunction "2_2") (pintype "passive"))
      (node (ref "R14") (pin "2") (pinfunction "2_2") (pintype "passive"))
      (node (ref "R15") (pin "2") (pinfunction "2_2") (pintype "passive"))
      (node (ref "R16") (pin "2") (pinfunction "2_2") (pintype "passive"))
      (node (ref "R17") (pin "2") (pinfunction "2_2") (pintype "passive"))
      (node (ref "R2") (pin "2") (pinfunction "2_2") (pintype "passive"))
      (node (ref "R25") (pin "1") (pinfunction "1_1") (pintype "passive"))
      (node (ref "R26") (pin "1") (pinfunction "1_1") (pintype "passive"))
      (node (ref "R27") (pin "1") (pinfunction "1_1") (pintype "passive"))
      (node (ref "R3") (pin "2") (pinfunction "2_2") (pintype "passive"))
      (node (ref "R4") (pin "2") (pinfunction "2_2") (pintype "passive"))
      (node (ref "R5") (pin "2") (pinfunction "2_2") (pintype "passive"))
      (node (ref "U10") (pin "1") (pinfunction "1_1") (pintype "passive"))
      (node (ref "U10") (pin "3") (pinfunction "3_3") (pintype "passive"))
      (node (ref "U10") (pin "5") (pinfunction "5_5") (pintype "passive"))
      (node (ref "U10") (pin "7") (pinfunction "7_7") (pintype "passive"))
      (node (ref "U15") (pin "1") (pinfunction "1_1") (pintype "passive"))
      (node (ref "U15") (pin "2") (pinfunction "2_2") (pintype "passive"))
      (node (ref "U21") (pin "4") (pinfunction "TAB_4") (pintype "passive"))
      (node (ref "U3") (pin "2") (pinfunction "3V3_2") (pintype "passive"))
    )
    (net (code "48") (name "GND") (class "Default")
      (node (ref "BOOT") (pin "1") (pinfunction "1_1") (pintype "passive"))
      (node (ref "C1") (pin "1") (pinfunction "1_1") (pintype "passive"))
      (node (ref "C10") (pin "1") (pinfunction "1_1") (pintype "passive"))
      (node (ref "C11") (pin "1") (pinfunction "1_1") (pintype "passive"))
      (node (ref "C12") (pin "2") (pinfunction "2_2") (pintype "passive"))
      (node (ref "C2") (pin "1") (pinfunction "1_1") (pintype "passive"))
      (node (ref "C3") (pin "1") (pinfunction "1_1") (pintype "passive"))
      (node (ref "C4") (pin "1") (pinfunction "1_1") (pintype "passive"))
      (node (ref "C5") (pin "2") (pinfunction "2_2") (pintype "passive"))
      (node (ref "C6") (pin "1") (pinfunction "1_1") (pintype "passive"))
      (node (ref "C7") (pin "1") (pinfunction "1_1") (pintype "passive"))
      (node (ref "C8") (pin "1") (pinfunction "1_1") (pintype "passive"))
      (node (ref "C9") (pin "2") (pinfunction "2_2") (pintype "passive"))
      (node (ref "D7") (pin "1") (pinfunction "1_1") (pintype "passive"))
      (node (ref "LED1") (pin "2") (pinfunction "K_2") (pintype "passive"))
      (node (ref "LED2") (pin "1") (pinfunction "-_1") (pintype "passive"))
      (node (ref "MH1") (pin "1") (pinfunction "GND_1") (pintype "passive"))
      (node (ref "MH2") (pin "1") (pinfunction "GND_1") (pintype "passive"))
      (node (ref "MH3") (pin "1") (pinfunction "GND_1") (pintype "passive"))
      (node (ref "MH4") (pin "1") (pinfunction "GND_1") (pintype "passive"))
      (node (ref "Q1") (pin "2") (pinfunction "E_2") (pintype "passive"))
      (node (ref "Q2") (pin "2") (pinfunction "E_2") (pintype "passive"))
      (node (ref "Q3") (pin "2") (pinfunction "E_2") (pintype "passive"))
      (node (ref "Q4") (pin "2") (pinfunction "E_2") (pintype "passive"))
      (node (ref "Q5") (pin "2") (pinfunction "E_2") (pintype "passive"))
      (node (ref "Q6") (pin "2") (pinfunction "E_2") (pintype "passive"))
      (node (ref "Q7") (pin "2") (pinfunction "E_2") (pintype "passive"))
      (node (ref "Q8") (pin "2") (pinfunction "E_2") (pintype "passive"))
      (node (ref "R10") (pin "1") (pinfunction "1_1") (pintype "passive"))
      (node (ref "R11") (pin "1") (pinfunction "1_1") (pintype "passive"))
      (node (ref "R23") (pin "1") (pinfunction "1_1") (pintype "passive"))
      (node (ref "R24") (pin "1") (pinfunction "1_1") (pintype "passive"))
      (node (ref "R32") (pin "1") (pinfunction "1_1") (pintype "passive"))
      (node (ref "R33") (pin "1") (pinfunction "1_1") (pintype "passive"))
      (node (ref "RESET") (pin "1") (pinfunction "1_1") (pintype "passive"))
      (node (ref "RGB") (pin "3") (pinfunction "GND_3") (pintype "passive"))
      (node (ref "U10") (pin "2") (pinfunction "2_2") (pintype "passive"))
      (node (ref "U10") (pin "4") (pinfunction "4_4") (pintype "passive"))
      (node (ref "U10") (pin "6") (pinfunction "6_6") (pintype "passive"))
      (node (ref "U10") (pin "8") (pinfunction "8_8") (pintype "passive"))
      (node (ref "U11") (pin "2") (pinfunction "2_2") (pintype "passive"))
      (node (ref "U11") (pin "4") (pinfunction "4_4") (pintype "passive"))
      (node (ref "U11") (pin "6") (pinfunction "6_6") (pintype "passive"))
      (node (ref "U11") (pin "8") (pinfunction "8_8") (pintype "passive"))
      (node (ref "U15") (pin "3") (pinfunction "3_3") (pintype "passive"))
      (node (ref "U15") (pin "4") (pinfunction "4_4") (pintype "passive"))
      (node (ref "U16") (pin "3") (pinfunction "3_3") (pintype "passive"))
      (node (ref "U16") (pin "4") (pinfunction "4_4") (pintype "passive"))
      (node (ref "U17") (pin "3") (pinfunction "GND_3") (pintype "passive"))
      (node (ref "U18") (pin "1") (pinfunction "1_1") (pintype "passive"))
      (node (ref "U20") (pin "4") (pinfunction "+VO_4") (pintype "passive"))
      (node (ref "U21") (pin "3") (pinfunction "VIN_3") (pintype "passive"))
      (node (ref "U22") (pin "2") (pinfunction "GND_2") (pintype "passive"))
      (node (ref "U22") (pin "3") (pinfunction "CTL_3") (pintype "passive"))
      (node (ref "U3") (pin "1") (pinfunction "GND_1") (pintype "passive"))
      (node (ref "U3") (pin "40") (pinfunction "GND_40") (pintype "passive"))
      (node (ref "U3") (pin "41") (pinfunction "GND_41") (pintype "passive"))
      (node (ref "USB1") (pin "1") (pinfunction "GND_1") (pintype "passive"))
      (node (ref "USB1") (pin "12") (pinfunction "GND_12") (pintype "passive"))
    )
    (net (code "49") (name "Net-(D1-A)") (class "Default")
      (node (ref "D1") (pin "2") (pinfunction "A_2") (pintype "passive"))
      (node (ref "K1") (pin "1") (pinfunction "1_1") (pintype "passive"))
      (node (ref "Q1") (pin "3") (pinfunction "C_3") (pintype "passive"))
    )
    (net (code "50") (name "Net-(D2-A)") (class "Default")
      (node (ref "D2") (pin "2") (pinfunction "A_2") (pintype "passive"))
      (node (ref "K2") (pin "1") (pinfunction "1_1") (pintype "passive"))
      (node (ref "Q2") (pin "3") (pinfunction "C_3") (pintype "passive"))
    )
    (net (code "51") (name "Net-(D3-A)") (class "Default")
      (node (ref "D3") (pin "2") (pinfunction "A_2") (pintype "passive"))
      (node (ref "K3") (pin "1") (pinfunction "1_1") (pintype "passive"))
      (node (ref "Q5") (pin "3") (pinfunction "C_3") (pintype "passive"))
    )
    (net (code "52") (name "Net-(D4-A)") (class "Default")
      (node (ref "D4") (pin "2") (pinfunction "A_2") (pintype "passive"))
      (node (ref "K4") (pin "1") (pinfunction "1_1") (pintype "passive"))
      (node (ref "Q6") (pin "3") (pinfunction "C_3") (pintype "passive"))
    )
    (net (code "53") (name "Net-(GREEN-+)") (class "Default")
      (node (ref "GREEN") (pin "1") (pinfunction "+_1") (pintype "passive"))
      (node (ref "R4") (pin "1") (pinfunction "1_1") (pintype "passive"))
    )
    (net (code "54") (name "Net-(GREEN--)") (class "Default")
      (node (ref "GREEN") (pin "2") (pinfunction "-_2") (pintype "passive"))
      (node (ref "Q3") (pin "3") (pinfunction "C_3") (pintype "passive"))
      (node (ref "U4") (pin "2") (pinfunction "CAT_2") (pintype "passive"))
    )
    (net (code "55") (name "Net-(GREEN1-+)") (class "Default")
      (node (ref "GREEN1") (pin "1") (pinfunction "+_1") (pintype "passive"))
      (node (ref "R5") (pin "1") (pinfunction "1_1") (pintype "passive"))
    )
    (net (code "56") (name "Net-(GREEN1--)") (class "Default")
      (node (ref "GREEN1") (pin "2") (pinfunction "-_2") (pintype "passive"))
      (node (ref "Q4") (pin "3") (pinfunction "C_3") (pintype "passive"))
      (node (ref "U5") (pin "2") (pinfunction "CAT_2") (pintype "passive"))
    )
    (net (code "57") (name "Net-(GREEN2-+)") (class "Default")
      (node (ref "GREEN2") (pin "1") (pinfunction "+_1") (pintype "passive"))
      (node (ref "R16") (pin "1") (pinfunction "1_1") (pintype "passive"))
    )
    (net (code "58") (name "Net-(GREEN2--)") (class "Default")
      (node (ref "GREEN2") (pin "2") (pinfunction "-_2") (pintype "passive"))
      (node (ref "Q7") (pin "3") (pinfunction "C_3") (pintype "passive"))
      (node (ref "U8") (pin "2") (pinfunction "CAT_2") (pintype "passive"))
    )
    (net (code "59") (name "Net-(GREEN3-+)") (class "Default")
      (node (ref "GREEN3") (pin "1") (pinfunction "+_1") (pintype "passive"))
      (node (ref "R17") (pin "1") (pinfunction "1_1") (pintype "passive"))
    )
    (net (code "60") (name "Net-(GREEN3--)") (class "Default")
      (node (ref "GREEN3") (pin "2") (pinfunction "-_2") (pintype "passive"))
      (node (ref "Q8") (pin "3") (pinfunction "C_3") (pintype "passive"))
      (node (ref "U9") (pin "2") (pinfunction "CAT_2") (pintype "passive"))
    )
    (net (code "61") (name "Net-(K1-COM)") (class "Default")
      (node (ref "K1") (pin "2") (pinfunction "COM_2") (pintype "passive"))
      (node (ref "U1") (pin "2") (pinfunction "2_2") (pintype "passive"))
    )
    (net (code "62") (name "Net-(K1-N.C.)") (class "Default")
      (node (ref "K1") (pin "4") (pinfunction "N.C._4") (pintype "passive"))
      (node (ref "U1") (pin "1") (pinfunction "1_1") (pintype "passive"))
    )
    (net (code "63") (name "Net-(K1-N.O.)") (class "Default")
      (node (ref "K1") (pin "3") (pinfunction "N.O._3") (pintype "passive"))
      (node (ref "U1") (pin "3") (pinfunction "3_3") (pintype "passive"))
    )
    (net (code "64") (name "Net-(K2-COM)") (class "Default")
      (node (ref "K2") (pin "2") (pinfunction "COM_2") (pintype "passive"))
      (node (ref "U2") (pin "2") (pinfunction "2_2") (pintype "passive"))
    )
    (net (code "65") (name "Net-(K2-N.C.)") (class "Default")
      (node (ref "K2") (pin "4") (pinfunction "N.C._4") (pintype "passive"))
      (node (ref "U2") (pin "1") (pinfunction "1_1") (pintype "passive"))
    )
    (net (code "66") (name "Net-(K2-N.O.)") (class "Default")
      (node (ref "K2") (pin "3") (pinfunction "N.O._3") (pintype "passive"))
      (node (ref "U2") (pin "3") (pinfunction "3_3") (pintype "passive"))
    )
    (net (code "67") (name "Net-(K3-COM)") (class "Default")
      (node (ref "K3") (pin "2") (pinfunction "COM_2") (pintype "passive"))
      (node (ref "U6") (pin "2") (pinfunction "2_2") (pintype "passive"))
    )
    (net (code "68") (name "Net-(K3-N.C.)") (class "Default")
      (node (ref "K3") (pin "4") (pinfunction "N.C._4") (pintype "passive"))
      (node (ref "U6") (pin "1") (pinfunction "1_1") (pintype "passive"))
    )
    (net (code "69") (name "Net-(K3-N.O.)") (class "Default")
      (node (ref "K3") (pin "3") (pinfunction "N.O._3") (pintype "passive"))
      (node (ref "U6") (pin "3") (pinfunction "3_3") (pintype "passive"))
    )
    (net (code "70") (name "Net-(K4-COM)") (class "Default")
      (node (ref "K4") (pin "2") (pinfunction "COM_2") (pintype "passive"))
      (node (ref "U7") (pin "2") (pinfunction "2_2") (pintype "passive"))
    )
    (net (code "71") (name "Net-(K4-N.C.)") (class "Default")
      (node (ref "K4") (pin "4") (pinfunction "N.C._4") (pintype "passive"))
      (node (ref "U7") (pin "1") (pinfunction "1_1") (pintype "passive"))
    )
    (net (code "72") (name "Net-(K4-N.O.)") (class "Default")
      (node (ref "K4") (pin "3") (pinfunction "N.O._3") (pintype "passive"))
      (node (ref "U7") (pin "3") (pinfunction "3_3") (pintype "passive"))
    )
    (net (code "73") (name "Net-(LED1-A)") (class "Default")
      (node (ref "LED1") (pin "1") (pinfunction "A_1") (pintype "passive"))
      (node (ref "R20") (pin "2") (pinfunction "2_2") (pintype "passive"))
    )
    (net (code "74") (name "Net-(LED2-+)") (class "Default")
      (node (ref "LED2") (pin "2") (pinfunction "+_2") (pintype "passive"))
      (node (ref "R25") (pin "2") (pinfunction "2_2") (pintype "passive"))
    )
    (net (code "75") (name "Net-(Q1-B)") (class "Default")
      (node (ref "Q1") (pin "1") (pinfunction "B_1") (pintype "passive"))
      (node (ref "R6") (pin "1") (pinfunction "1_1") (pintype "passive"))
    )
    (net (code "76") (name "Net-(Q2-B)") (class "Default")
      (node (ref "Q2") (pin "1") (pinfunction "B_1") (pintype "passive"))
      (node (ref "R7") (pin "1") (pinfunction "1_1") (pintype "passive"))
    )
    (net (code "77") (name "Net-(Q3-B)") (class "Default")
      (node (ref "Q3") (pin "1") (pinfunction "B_1") (pintype "passive"))
      (node (ref "R10") (pin "2") (pinfunction "2_2") (pintype "passive"))
      (node (ref "R8") (pin "1") (pinfunction "1_1") (pintype "passive"))
    )
    (net (code "78") (name "Net-(Q4-B)") (class "Default")
      (node (ref "Q4") (pin "1") (pinfunction "B_1") (pintype "passive"))
      (node (ref "R11") (pin "2") (pinfunction "2_2") (pintype "passive"))
      (node (ref "R9") (pin "1") (pinfunction "1_1") (pintype "passive"))
    )
    (net (code "79") (name "Net-(Q5-B)") (class "Default")
      (node (ref "Q5") (pin "1") (pinfunction "B_1") (pintype "passive"))
      (node (ref "R18") (pin "1") (pinfunction "1_1") (pintype "passive"))
    )
    (net (code "80") (name "Net-(Q6-B)") (class "Default")
      (node (ref "Q6") (pin "1") (pinfunction "B_1") (pintype "passive"))
      (node (ref "R19") (pin "1") (pinfunction "1_1") (pintype "passive"))
    )
    (net (code "81") (name "Net-(Q7-B)") (class "Default")
      (node (ref "Q7") (pin "1") (pinfunction "B_1") (pintype "passive"))
      (node (ref "R21") (pin "1") (pinfunction "1_1") (pintype "passive"))
      (node (ref "R23") (pin "2") (pinfunction "2_2") (pintype "passive"))
    )
    (net (code "82") (name "Net-(Q8-B)") (class "Default")
      (node (ref "Q8") (pin "1") (pinfunction "B_1") (pintype "passive"))
      (node (ref "R22") (pin "1") (pinfunction "1_1") (pintype "passive"))
      (node (ref "R24") (pin "2") (pinfunction "2_2") (pintype "passive"))
    )
    (net (code "83") (name "Net-(Q9-B)") (class "Default")
      (node (ref "Q9") (pin "1") (pinfunction "B_1") (pintype "passive"))
      (node (ref "R29") (pin "2") (pinfunction "2_2") (pintype "passive"))
    )
    (net (code "84") (name "Net-(Q9-C)") (class "Default")
      (node (ref "Q9") (pin "3") (pinfunction "C_3") (pintype "passive"))
      (node (ref "R28") (pin "1") (pinfunction "1_1") (pintype "passive"))
    )
    (net (code "85") (name "Net-(Q10-D)") (class "Default")
      (node (ref "F1") (pin "2") (pinfunction "2_2") (pintype "passive"))
      (node (ref "Q10") (pin "3") (pinfunction "D_3") (pintype "passive"))
      (node (ref "U22") (pin "1") (pinfunction "VIN_1") (pintype "passive"))
    )
    (net (code "86") (name "Net-(Q10-G)") (class "Default")
      (node (ref "Q10") (pin "1") (pinfunction "G_1") (pintype "passive"))
      (node (ref "U22") (pin "5") (pinfunction "GATE_5") (pintype "passive"))
    )
    (net (code "87") (name "Net-(Q11-B)") (class "Default")
      (node (ref "Q11") (pin "1") (pinfunction "B_1") (pintype "passive"))
      (node (ref "R30") (pin "2") (pinfunction "2_2") (pintype "passive"))
    )
    (net (code "88") (name "Net-(Q11-C)") (class "Default")
      (node (ref "Q11") (pin "3") (pinfunction "C_3") (pintype "passive"))
      (node (ref "R31") (pin "1") (pinfunction "1_1") (pintype "passive"))
    )
    (net (code "89") (name "Net-(RX-+)") (class "Default")
      (node (ref "R27") (pin "2") (pinfunction "2_2") (pintype "passive"))
      (node (ref "RX") (pin "1") (pinfunction "+_1") (pintype "passive"))
    )
    (net (code "90") (name "Net-(TX-A)") (class "Default")
      (node (ref "R26") (pin "2") (pinfunction "2_2") (pintype "passive"))
      (node (ref "TX") (pin "2") (pinfunction "A_2") (pintype "passive"))
    )
    (net (code "91") (name "Net-(U4-AN)") (class "Default")
      (node (ref "R2") (pin "1") (pinfunction "1_1") (pintype "passive"))
      (node (ref "U4") (pin "1") (pinfunction "AN_1") (pintype "passive"))
    )
    (net (code "92") (name "Net-(U4-EMI)") (class "Default")
      (node (ref "R6") (pin "2") (pinfunction "2_2") (pintype "passive"))
      (node (ref "U4") (pin "3") (pinfunction "EMI_3") (pintype "passive"))
    )
    (net (code "93") (name "Net-(U5-AN)") (class "Default")
      (node (ref "R3") (pin "1") (pinfunction "1_1") (pintype "passive"))
      (node (ref "U5") (pin "1") (pinfunction "AN_1") (pintype "passive"))
    )
    (net (code "94") (name "Net-(U5-EMI)") (class "Default")
      (node (ref "R7") (pin "2") (pinfunction "2_2") (pintype "passive"))
      (node (ref "U5") (pin "3") (pinfunction "EMI_3") (pintype "passive"))
    )
    (net (code "95") (name "Net-(U8-AN)") (class "Default")
      (node (ref "R14") (pin "1") (pinfunction "1_1") (pintype "passive"))
      (node (ref "U8") (pin "1") (pinfunction "AN_1") (pintype "passive"))
    )
    (net (code "96") (name "Net-(U8-EMI)") (class "Default")
      (node (ref "R18") (pin "2") (pinfunction "2_2") (pintype "passive"))
      (node (ref "U8") (pin "3") (pinfunction "EMI_3") (pintype "passive"))
    )
    (net (code "97") (name "Net-(U9-AN)") (class "Default")
      (node (ref "R15") (pin "1") (pinfunction "1_1") (pintype "passive"))
      (node (ref "U9") (pin "1") (pinfunction "AN_1") (pintype "passive"))
    )
    (net (code "98") (name "Net-(U9-EMI)") (class "Default")
      (node (ref "R19") (pin "2") (pinfunction "2_2") (pintype "passive"))
      (node (ref "U9") (pin "3") (pinfunction "EMI_3") (pintype "passive"))
    )
    (net (code "99") (name "Net-(U17-VDD)") (class "Default")
      (node (ref "C4") (pin "2") (pinfunction "2_2") (pintype "passive"))
      (node (ref "U17") (pin "6") (pinfunction "VDD_6") (pintype "passive"))
    )
    (net (code "100") (name "Net-(U19-Pad1)") (class "Default")
      (node (ref "U19") (pin "1") (pinfunction "1_1") (pintype "passive"))
      (node (ref "U20") (pin "2") (pinfunction "AC_2") (pintype "passive"))
    )
    (net (code "101") (name "Net-(U19-Pad2)") (class "Default")
      (node (ref "U19") (pin "2") (pinfunction "2_2") (pintype "passive"))
      (node (ref "U20") (pin "1") (pinfunction "AC_1") (pintype "passive"))
    )
    (net (code "102") (name "Net-(U20--VO)") (class "Default")
      (node (ref "F1") (pin "1") (pinfunction "1_1") (pintype "passive"))
      (node (ref "U20") (pin "3") (pinfunction "-VO_3") (pintype "passive"))
    )
    (net (code "103") (name "unconnected-(RGB-DOU-Pad2)") (class "Default")
      (node (ref "RGB") (pin "2") (pinfunction "DOU_2") (pintype "passive+no_connect"))
    )
    (net (code "104") (name "unconnected-(U17-CTS-Pad23)") (class "Default")
      (node (ref "U17") (pin "23") (pinfunction "CTS_23") (pintype "passive+no_connect"))
    )
    (net (code "105") (name "unconnected-(U17-DCD-Pad1)") (class "Default")
      (node (ref "U17") (pin "1") (pinfunction "DCD_1") (pintype "passive+no_connect"))
    )
    (net (code "106") (name "unconnected-(U17-DSR-Pad27)") (class "Default")
      (node (ref "U17") (pin "27") (pinfunction "DSR_27") (pintype "passive+no_connect"))
    )
    (net (code "107") (name "unconnected-(U17-EP-Pad29)") (class "Default")
      (node (ref "U17") (pin "29") (pinfunction "EP_29") (pintype "passive+no_connect"))
    )
    (net (code "108") (name "unconnected-(U17-NC-Pad10)") (class "Default")
      (node (ref "U17") (pin "10") (pinfunction "NC_10") (pintype "passive+no_connect"))
    )
    (net (code "109") (name "unconnected-(U17-NC-Pad13)") (class "Default")
      (node (ref "U17") (pin "13") (pinfunction "NC_13") (pintype "passive+no_connect"))
    )
    (net (code "110") (name "unconnected-(U17-NC-Pad14)") (class "Default")
      (node (ref "U17") (pin "14") (pinfunction "NC_14") (pintype "passive+no_connect"))
    )
    (net (code "111") (name "unconnected-(U17-NC-Pad15)") (class "Default")
      (node (ref "U17") (pin "15") (pinfunction "NC_15") (pintype "passive+no_connect"))
    )
    (net (code "112") (name "unconnected-(U17-NC-Pad16)") (class "Default")
      (node (ref "U17") (pin "16") (pinfunction "NC_16") (pintype "passive+no_connect"))
    )
    (net (code "113") (name "unconnected-(U17-NC-Pad17)") (class "Default")
      (node (ref "U17") (pin "17") (pinfunction "NC_17") (pintype "passive+no_connect"))
    )
    (net (code "114") (name "unconnected-(U17-NC-Pad18)") (class "Default")
      (node (ref "U17") (pin "18") (pinfunction "NC_18") (pintype "passive+no_connect"))
    )
    (net (code "115") (name "unconnected-(U17-NC-Pad19)") (class "Default")
      (node (ref "U17") (pin "19") (pinfunction "NC_19") (pintype "passive+no_connect"))
    )
    (net (code "116") (name "unconnected-(U17-NC-Pad20)") (class "Default")
      (node (ref "U17") (pin "20") (pinfunction "NC_20") (pintype "passive+no_connect"))
    )
    (net (code "117") (name "unconnected-(U17-NC-Pad21)") (class "Default")
      (node (ref "U17") (pin "21") (pinfunction "NC_21") (pintype "passive+no_connect"))
    )
    (net (code "118") (name "unconnected-(U17-NC-Pad22)") (class "Default")
      (node (ref "U17") (pin "22") (pinfunction "NC_22") (pintype "passive+no_connect"))
    )
    (net (code "119") (name "unconnected-(U17-RI-Pad2)") (class "Default")
      (node (ref "U17") (pin "2") (pinfunction "RI_2") (pintype "passive+no_connect"))
    )
    (net (code "120") (name "unconnected-(U17-RST#-Pad9)") (class "Default")
      (node (ref "U17") (pin "9") (pinfunction "RST#_9") (pintype "passive+no_connect"))
    )
    (net (code "121") (name "unconnected-(U17-SUSPEND#-Pad11)") (class "Default")
      (node (ref "U17") (pin "11") (pinfunction "SUSPEND#_11") (pintype "passive+no_connect"))
    )
    (net (code "122") (name "unconnected-(U17-SUSPEND-Pad12)") (class "Default")
      (node (ref "U17") (pin "12") (pinfunction "SUSPEND_12") (pintype "passive+no_connect"))
    )
    (net (code "123") (name "unconnected-(U21-VOUT(TAB)-Pad2)") (class "Default")
      (node (ref "U21") (pin "2") (pinfunction "VOUT(TAB)_2") (pintype "passive+no_connect"))
    )
    (net (code "124") (name "unconnected-(U22-STAT-Pad4)") (class "Default")
      (node (ref "U22") (pin "4") (pinfunction "STAT_4") (pintype "passive+no_connect"))
    )
    (net (code "125") (name "unconnected-(USB1-SBU1-Pad9)") (class "Default")
      (node (ref "USB1") (pin "9") (pinfunction "SBU1_9") (pintype "passive+no_connect"))
    )
    (net (code "126") (name "unconnected-(USB1-SBU2-Pad3)") (class "Default")
      (node (ref "USB1") (pin "3") (pinfunction "SBU2_3") (pintype "passive+no_connect"))
    )
    (net (code "127") (name "unconnected-(USB1-SHELL-Pad13)") (class "Default")
      (node (ref "USB1") (pin "13") (pinfunction "SHELL_13") (pintype "passive+no_connect"))
    )
    (net (code "128") (name "unconnected-(USB1-SHELL-Pad14)") (class "Default")
      (node (ref "USB1") (pin "14") (pinfunction "SHELL_14") (pintype "passive+no_connect"))
    )
  )
)
